# ASD2021.net
KiCad netlist of a schematic drawn in EAGLE
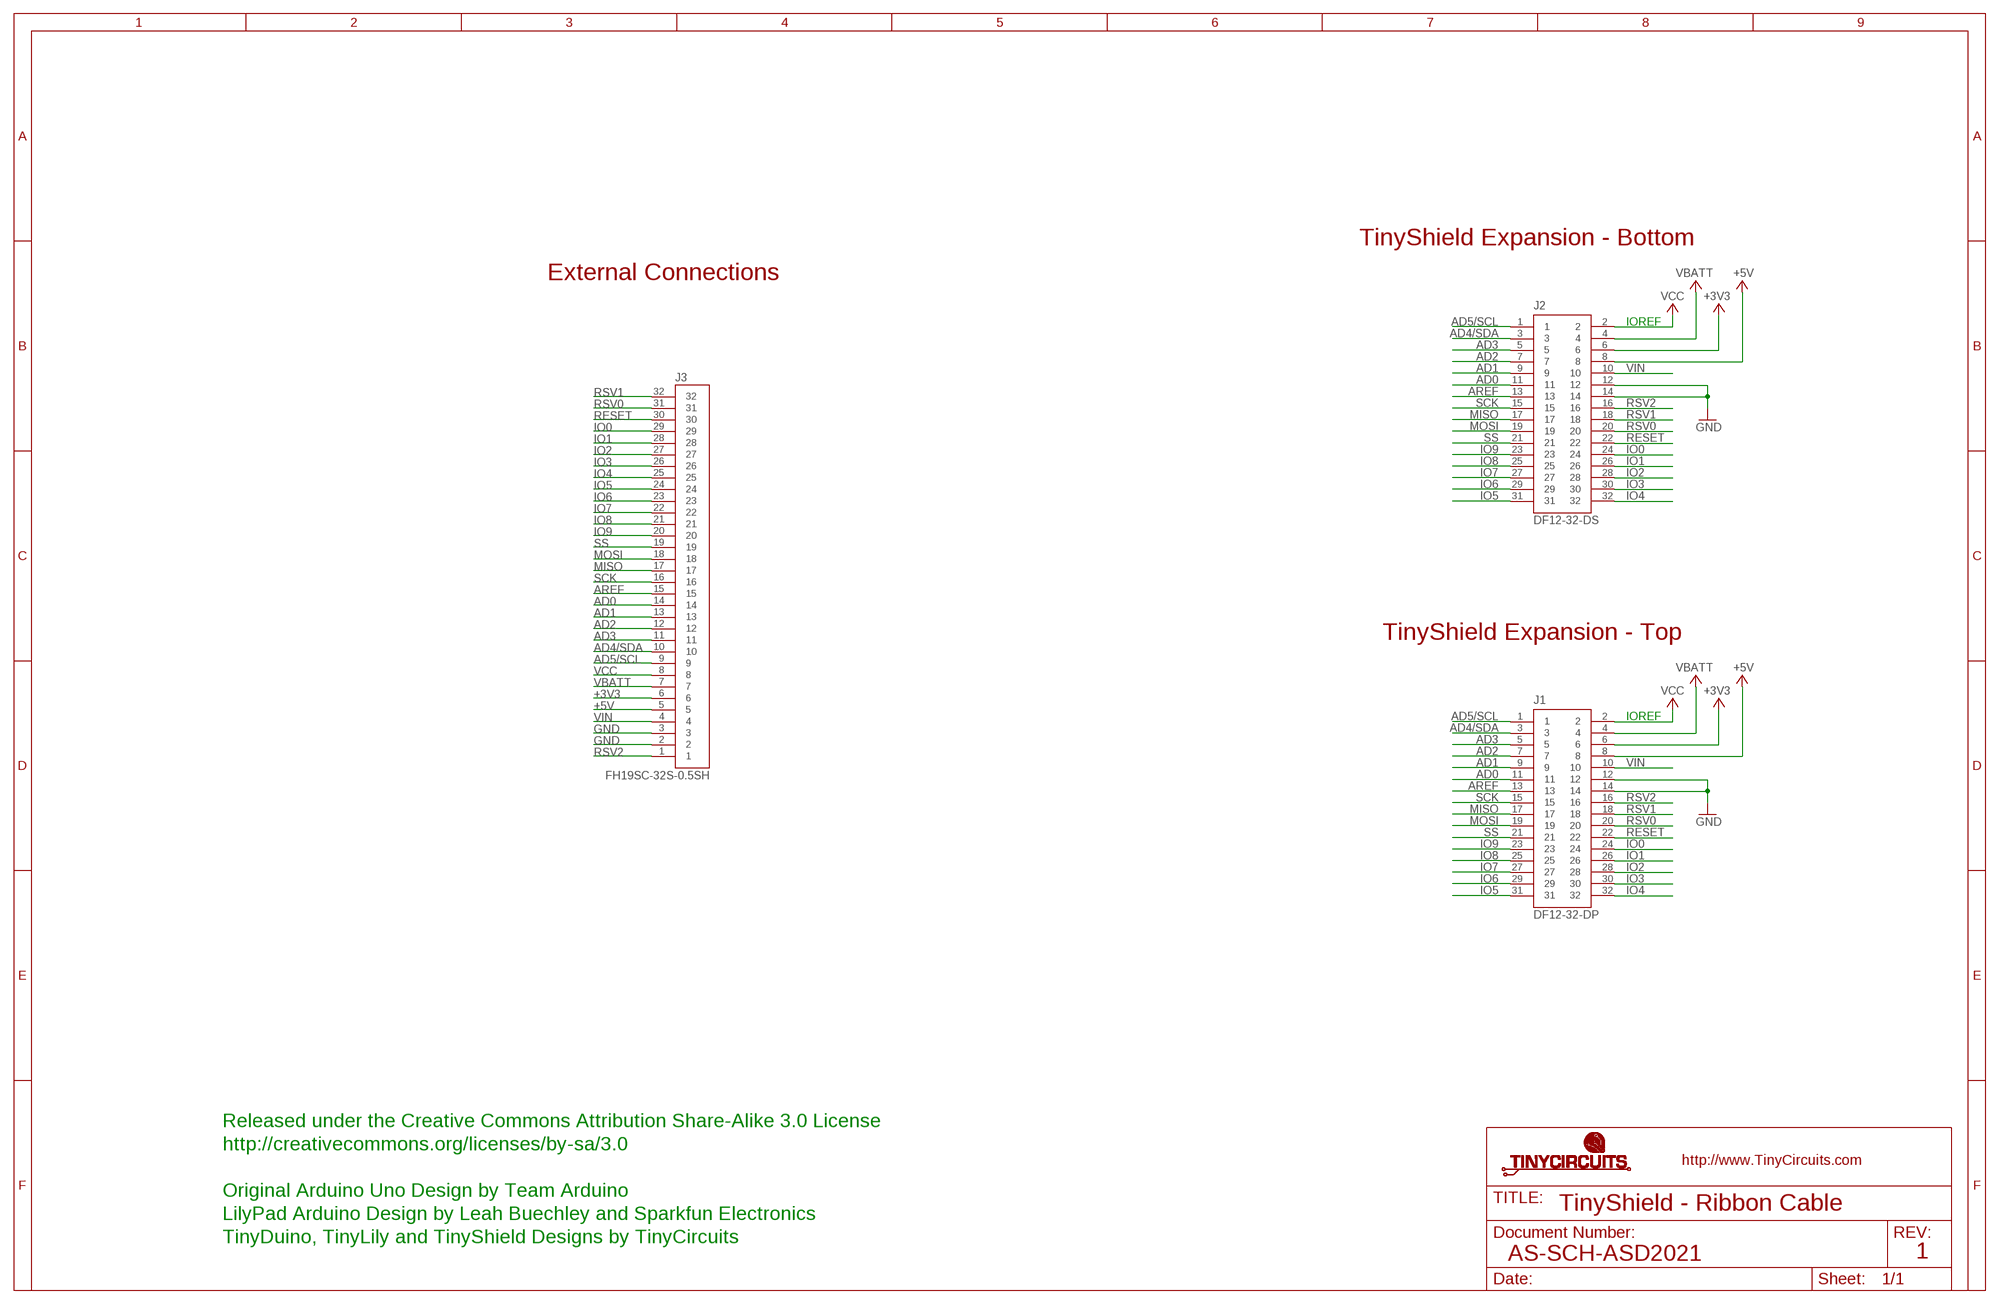
[diagram p0: schematic, sheet 1]

(export (version "E")
  (design (tool "Eeschema 10.0.6"))
  (components
    (comp (ref "J1")
      (value "DF12-32-DP")
      (footprint "eagle-import:DF12-32-DP")
      (fields (field (name "PARTNO") "AS-ITM-00015") (field (name "PARTNO_1") "AS-ITM-00015"))
      (libsource (lib "eagle-import") (part "AS-ITM-00015"))
    )
    (comp (ref "J2")
      (value "DF12-32-DS")
      (footprint "eagle-import:DF12-32-DS")
      (fields (field (name "PARTNO") "AS-ITM-00012") (field (name "PARTNO_1") "AS-ITM-00012"))
      (libsource (lib "eagle-import") (part "AS-ITM-00012"))
    )
    (comp (ref "J3")
      (value "FH19SC-32S-0.5SH")
      (footprint "eagle-import:FH19SC-32S-0.5SH")
      (fields (field (name "PARTNO") "AS-ITM-00234"))
      (libsource (lib "eagle-import") (part "AS-ITM-00234"))
    )
  )
  (nets
    (net (code "1") (name "+3V3") (class "Default")
      (node (ref "J1") (pin "6") (pinfunction "6_6") (pintype "bidirectional"))
      (node (ref "J2") (pin "6") (pinfunction "6_6") (pintype "bidirectional"))
      (node (ref "J3") (pin "6") (pinfunction "6_6") (pintype "bidirectional"))
    )
    (net (code "2") (name "+5V") (class "Default")
      (node (ref "J1") (pin "8") (pinfunction "8_8") (pintype "bidirectional"))
      (node (ref "J2") (pin "8") (pinfunction "8_8") (pintype "bidirectional"))
      (node (ref "J3") (pin "5") (pinfunction "5_5") (pintype "bidirectional"))
    )
    (net (code "3") (name "/AD0") (class "Default")
      (node (ref "J1") (pin "11") (pinfunction "11_11") (pintype "bidirectional"))
      (node (ref "J2") (pin "11") (pinfunction "11_11") (pintype "bidirectional"))
      (node (ref "J3") (pin "14") (pinfunction "14_14") (pintype "bidirectional"))
    )
    (net (code "4") (name "/AD1") (class "Default")
      (node (ref "J1") (pin "9") (pinfunction "9_9") (pintype "bidirectional"))
      (node (ref "J2") (pin "9") (pinfunction "9_9") (pintype "bidirectional"))
      (node (ref "J3") (pin "13") (pinfunction "13_13") (pintype "bidirectional"))
    )
    (net (code "5") (name "/AD2") (class "Default")
      (node (ref "J1") (pin "7") (pinfunction "7_7") (pintype "bidirectional"))
      (node (ref "J2") (pin "7") (pinfunction "7_7") (pintype "bidirectional"))
      (node (ref "J3") (pin "12") (pinfunction "12_12") (pintype "bidirectional"))
    )
    (net (code "6") (name "/AD3") (class "Default")
      (node (ref "J1") (pin "5") (pinfunction "5_5") (pintype "bidirectional"))
      (node (ref "J2") (pin "5") (pinfunction "5_5") (pintype "bidirectional"))
      (node (ref "J3") (pin "11") (pinfunction "11_11") (pintype "bidirectional"))
    )
    (net (code "7") (name "/AD4{slash}SDA") (class "Default")
      (node (ref "J1") (pin "3") (pinfunction "3_3") (pintype "bidirectional"))
      (node (ref "J2") (pin "3") (pinfunction "3_3") (pintype "bidirectional"))
      (node (ref "J3") (pin "10") (pinfunction "10_10") (pintype "bidirectional"))
    )
    (net (code "8") (name "/AD5{slash}SCL") (class "Default")
      (node (ref "J1") (pin "1") (pinfunction "1_1") (pintype "bidirectional"))
      (node (ref "J2") (pin "1") (pinfunction "1_1") (pintype "bidirectional"))
      (node (ref "J3") (pin "9") (pinfunction "9_9") (pintype "bidirectional"))
    )
    (net (code "9") (name "/AREF") (class "Default")
      (node (ref "J1") (pin "13") (pinfunction "13_13") (pintype "bidirectional"))
      (node (ref "J2") (pin "13") (pinfunction "13_13") (pintype "bidirectional"))
      (node (ref "J3") (pin "15") (pinfunction "15_15") (pintype "bidirectional"))
    )
    (net (code "10") (name "/IO0") (class "Default")
      (node (ref "J1") (pin "24") (pinfunction "24_24") (pintype "bidirectional"))
      (node (ref "J2") (pin "24") (pinfunction "24_24") (pintype "bidirectional"))
      (node (ref "J3") (pin "29") (pinfunction "29_29") (pintype "bidirectional"))
    )
    (net (code "11") (name "/IO1") (class "Default")
      (node (ref "J1") (pin "26") (pinfunction "26_26") (pintype "bidirectional"))
      (node (ref "J2") (pin "26") (pinfunction "26_26") (pintype "bidirectional"))
      (node (ref "J3") (pin "28") (pinfunction "28_28") (pintype "bidirectional"))
    )
    (net (code "12") (name "/IO2") (class "Default")
      (node (ref "J1") (pin "28") (pinfunction "28_28") (pintype "bidirectional"))
      (node (ref "J2") (pin "28") (pinfunction "28_28") (pintype "bidirectional"))
      (node (ref "J3") (pin "27") (pinfunction "27_27") (pintype "bidirectional"))
    )
    (net (code "13") (name "/IO3") (class "Default")
      (node (ref "J1") (pin "30") (pinfunction "30_30") (pintype "bidirectional"))
      (node (ref "J2") (pin "30") (pinfunction "30_30") (pintype "bidirectional"))
      (node (ref "J3") (pin "26") (pinfunction "26_26") (pintype "bidirectional"))
    )
    (net (code "14") (name "/IO4") (class "Default")
      (node (ref "J1") (pin "32") (pinfunction "32_32") (pintype "bidirectional"))
      (node (ref "J2") (pin "32") (pinfunction "32_32") (pintype "bidirectional"))
      (node (ref "J3") (pin "25") (pinfunction "25_25") (pintype "bidirectional"))
    )
    (net (code "15") (name "/IO5") (class "Default")
      (node (ref "J1") (pin "31") (pinfunction "31_31") (pintype "bidirectional"))
      (node (ref "J2") (pin "31") (pinfunction "31_31") (pintype "bidirectional"))
      (node (ref "J3") (pin "24") (pinfunction "24_24") (pintype "bidirectional"))
    )
    (net (code "16") (name "/IO6") (class "Default")
      (node (ref "J1") (pin "29") (pinfunction "29_29") (pintype "bidirectional"))
      (node (ref "J2") (pin "29") (pinfunction "29_29") (pintype "bidirectional"))
      (node (ref "J3") (pin "23") (pinfunction "23_23") (pintype "bidirectional"))
    )
    (net (code "17") (name "/IO7") (class "Default")
      (node (ref "J1") (pin "27") (pinfunction "27_27") (pintype "bidirectional"))
      (node (ref "J2") (pin "27") (pinfunction "27_27") (pintype "bidirectional"))
      (node (ref "J3") (pin "22") (pinfunction "22_22") (pintype "bidirectional"))
    )
    (net (code "18") (name "/IO8") (class "Default")
      (node (ref "J1") (pin "25") (pinfunction "25_25") (pintype "bidirectional"))
      (node (ref "J2") (pin "25") (pinfunction "25_25") (pintype "bidirectional"))
      (node (ref "J3") (pin "21") (pinfunction "21_21") (pintype "bidirectional"))
    )
    (net (code "19") (name "/IO9") (class "Default")
      (node (ref "J1") (pin "23") (pinfunction "23_23") (pintype "bidirectional"))
      (node (ref "J2") (pin "23") (pinfunction "23_23") (pintype "bidirectional"))
      (node (ref "J3") (pin "20") (pinfunction "20_20") (pintype "bidirectional"))
    )
    (net (code "20") (name "/MISO") (class "Default")
      (node (ref "J1") (pin "17") (pinfunction "17_17") (pintype "bidirectional"))
      (node (ref "J2") (pin "17") (pinfunction "17_17") (pintype "bidirectional"))
      (node (ref "J3") (pin "17") (pinfunction "17_17") (pintype "bidirectional"))
    )
    (net (code "21") (name "/MOSI") (class "Default")
      (node (ref "J1") (pin "19") (pinfunction "19_19") (pintype "bidirectional"))
      (node (ref "J2") (pin "19") (pinfunction "19_19") (pintype "bidirectional"))
      (node (ref "J3") (pin "18") (pinfunction "18_18") (pintype "bidirectional"))
    )
    (net (code "22") (name "/RESET") (class "Default")
      (node (ref "J1") (pin "22") (pinfunction "22_22") (pintype "bidirectional"))
      (node (ref "J2") (pin "22") (pinfunction "22_22") (pintype "bidirectional"))
      (node (ref "J3") (pin "30") (pinfunction "30_30") (pintype "bidirectional"))
    )
    (net (code "23") (name "/RSV0") (class "Default")
      (node (ref "J1") (pin "20") (pinfunction "20_20") (pintype "bidirectional"))
      (node (ref "J2") (pin "20") (pinfunction "20_20") (pintype "bidirectional"))
      (node (ref "J3") (pin "31") (pinfunction "31_31") (pintype "bidirectional"))
    )
    (net (code "24") (name "/RSV1") (class "Default")
      (node (ref "J1") (pin "18") (pinfunction "18_18") (pintype "bidirectional"))
      (node (ref "J2") (pin "18") (pinfunction "18_18") (pintype "bidirectional"))
      (node (ref "J3") (pin "32") (pinfunction "32_32") (pintype "bidirectional"))
    )
    (net (code "25") (name "/RSV2") (class "Default")
      (node (ref "J1") (pin "16") (pinfunction "16_16") (pintype "bidirectional"))
      (node (ref "J2") (pin "16") (pinfunction "16_16") (pintype "bidirectional"))
      (node (ref "J3") (pin "1") (pinfunction "1_1") (pintype "bidirectional"))
    )
    (net (code "26") (name "/SCK") (class "Default")
      (node (ref "J1") (pin "15") (pinfunction "15_15") (pintype "bidirectional"))
      (node (ref "J2") (pin "15") (pinfunction "15_15") (pintype "bidirectional"))
      (node (ref "J3") (pin "16") (pinfunction "16_16") (pintype "bidirectional"))
    )
    (net (code "27") (name "/SS") (class "Default")
      (node (ref "J1") (pin "21") (pinfunction "21_21") (pintype "bidirectional"))
      (node (ref "J2") (pin "21") (pinfunction "21_21") (pintype "bidirectional"))
      (node (ref "J3") (pin "19") (pinfunction "19_19") (pintype "bidirectional"))
    )
    (net (code "28") (name "/VIN") (class "Default")
      (node (ref "J1") (pin "10") (pinfunction "10_10") (pintype "bidirectional"))
      (node (ref "J2") (pin "10") (pinfunction "10_10") (pintype "bidirectional"))
      (node (ref "J3") (pin "4") (pinfunction "4_4") (pintype "bidirectional"))
    )
    (net (code "29") (name "GND") (class "Default")
      (node (ref "J1") (pin "12") (pinfunction "12_12") (pintype "bidirectional"))
      (node (ref "J1") (pin "14") (pinfunction "14_14") (pintype "bidirectional"))
      (node (ref "J2") (pin "12") (pinfunction "12_12") (pintype "bidirectional"))
      (node (ref "J2") (pin "14") (pinfunction "14_14") (pintype "bidirectional"))
      (node (ref "J3") (pin "2") (pinfunction "2_2") (pintype "bidirectional"))
      (node (ref "J3") (pin "3") (pinfunction "3_3") (pintype "bidirectional"))
    )
    (net (code "30") (name "VBATT") (class "Default")
      (node (ref "J1") (pin "4") (pinfunction "4_4") (pintype "bidirectional"))
      (node (ref "J2") (pin "4") (pinfunction "4_4") (pintype "bidirectional"))
      (node (ref "J3") (pin "7") (pinfunction "7_7") (pintype "bidirectional"))
    )
    (net (code "31") (name "VCC") (class "Default")
      (node (ref "J1") (pin "2") (pinfunction "2_2") (pintype "bidirectional"))
      (node (ref "J2") (pin "2") (pinfunction "2_2") (pintype "bidirectional"))
      (node (ref "J3") (pin "8") (pinfunction "8_8") (pintype "bidirectional"))
    )
  )
)
